# LTE.net
KiCad netlist of a schematic drawn in Altium Designer
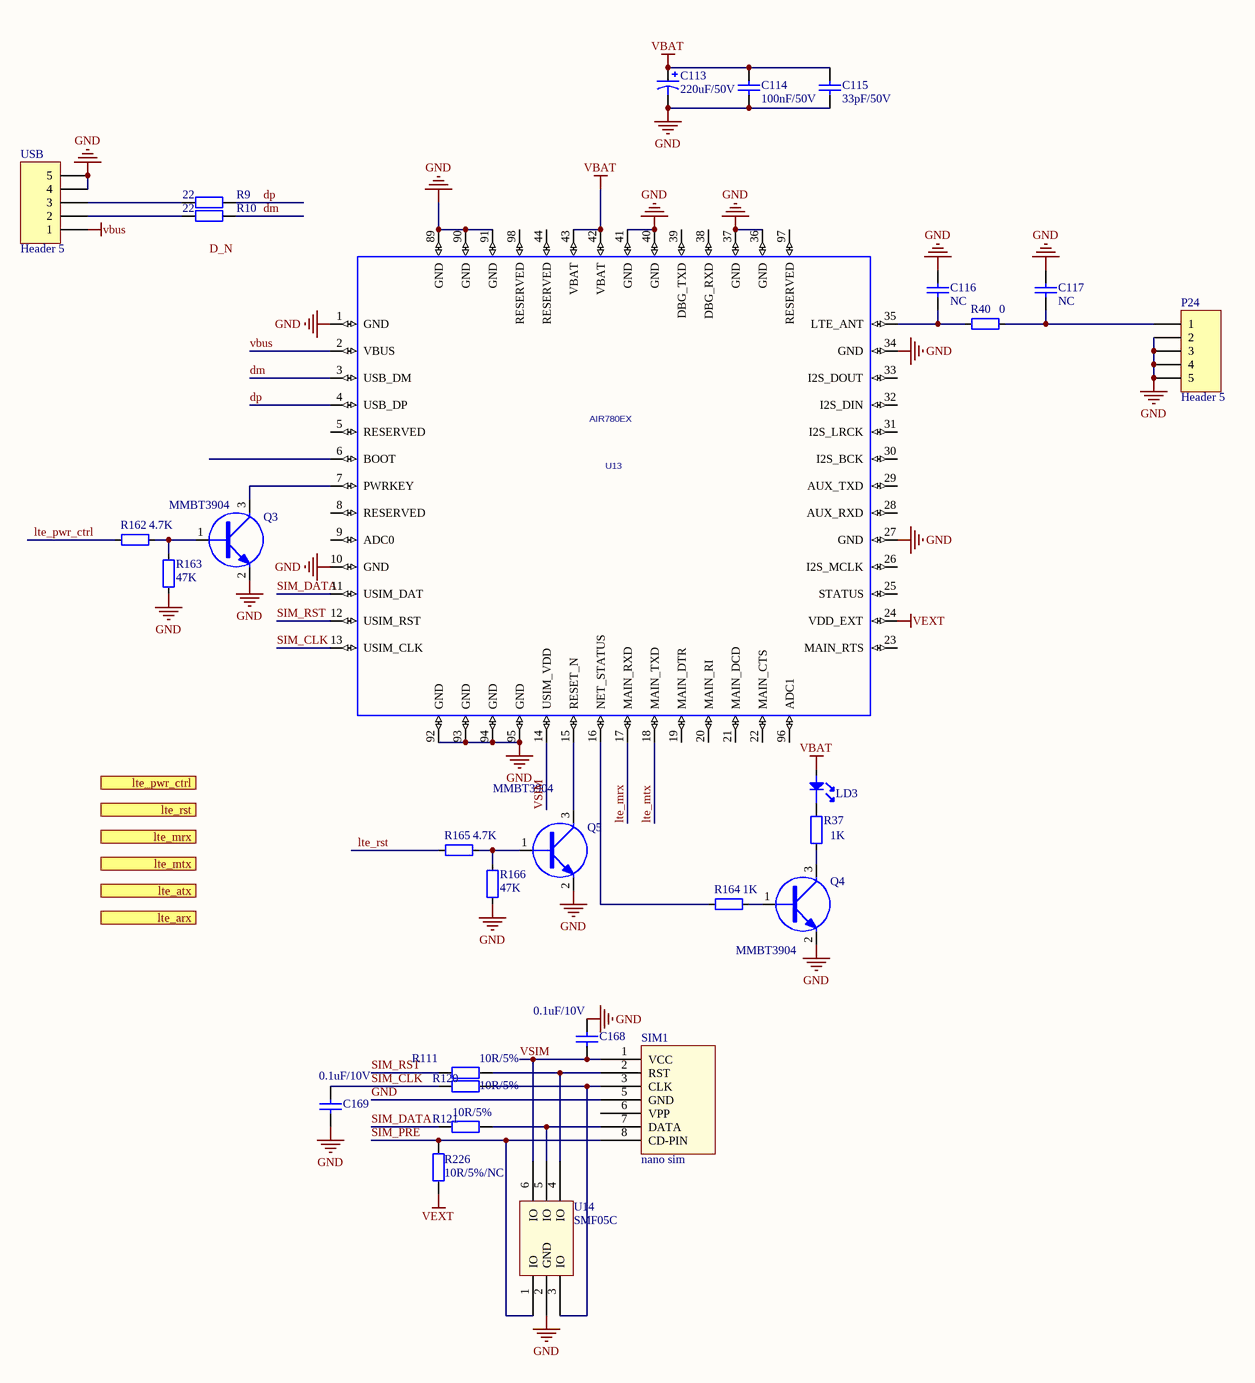
[diagram p0: LTE.SchDoc]

(export (version "E")
  (design (tool "Eeschema 10.0.6"))
  (components
    (comp (ref "C113")
      (value "220uF/50V")
      (footprint "Φ10×10")
      (description "Polarized Capacitor (Radial)")
      (fields (field (name "PUBLISHER") "Altium Limited"))
      (libsource (lib "Miscellaneous Devices") (part "Cap Pol1"))
    )
    (comp (ref "C114")
      (value "100nF/50V")
      (footprint "0603C")
      (description "Capacitor")
      (fields (field (name "PUBLISHER") "Altium Limited"))
      (libsource (lib "Miscellaneous Devices") (part "Cap"))
    )
    (comp (ref "C115")
      (value "33pF/50V")
      (footprint "0603C")
      (description "Capacitor")
      (fields (field (name "PUBLISHER") "Altium Limited"))
      (libsource (lib "Miscellaneous Devices") (part "Cap"))
    )
    (comp (ref "C116")
      (value "NC")
      (footprint "0603c")
      (description "Capacitor")
      (fields (field (name "PUBLISHER") "Altium Limited"))
      (libsource (lib "Miscellaneous Devices") (part "Cap"))
    )
    (comp (ref "C117")
      (value "NC")
      (footprint "0603c")
      (description "Capacitor")
      (fields (field (name "PUBLISHER") "Altium Limited"))
      (libsource (lib "Miscellaneous Devices") (part "Cap"))
    )
    (comp (ref "C168")
      (value "0.1uF/10V")
      (footprint "0603c")
      (description "Capacitor")
      (fields (field (name "PUBLISHER") "Altium Limited"))
      (libsource (lib "Miscellaneous Devices") (part "Cap"))
    )
    (comp (ref "C169")
      (value "0.1uF/10V")
      (footprint "0603c")
      (description "Capacitor")
      (fields (field (name "PUBLISHER") "Altium Limited"))
      (libsource (lib "Miscellaneous Devices") (part "Cap"))
    )
    (comp (ref "LD3")
      (value "LED_Green_19-217")
      (footprint "0603led")
      (libsource (lib "RC_M_D_00") (part "LED_Green_19-217"))
    )
    (comp (ref "P24")
      (value "Header 5")
      (footprint "KH-SMA-KE-Z")
      (description "Header, 5-Pin")
      (fields (field (name "PUBLISHER") "Altium Limited"))
      (libsource (lib "") (part "Header 5_1"))
    )
    (comp (ref "Q3")
      (value "MMBT3904")
      (footprint "SOT23-3")
      (libsource (lib "CenLib") (part "NPN_MMBT3904"))
    )
    (comp (ref "Q4")
      (value "MMBT3904")
      (footprint "SOT23-3")
      (libsource (lib "CenLib") (part "NPN_MMBT3904"))
    )
    (comp (ref "Q5")
      (value "MMBT3904")
      (footprint "SOT23-3")
      (libsource (lib "CenLib") (part "NPN_MMBT3904"))
    )
    (comp (ref "R9")
      (value "22")
      (footprint "0402R")
      (description "Resistor SMD - IEC symbol version")
      (libsource (lib "SX1276_e266v02a") (part "Resistor"))
    )
    (comp (ref "R10")
      (value "22")
      (footprint "0402R")
      (description "Resistor SMD - IEC symbol version")
      (libsource (lib "SX1276_e266v02a") (part "Resistor"))
    )
    (comp (ref "R37") (value "1K") (footprint "0603R") (libsource (lib "RC_M_D_00") (part "RES0603")))
    (comp (ref "R40") (value "0") (footprint "0603r") (libsource (lib "RC_M_D_00") (part "RES0603")))
    (comp (ref "R111")
      (value "10R/5%")
      (footprint "0603r")
      (description "Resistor")
      (fields (field (name "PUBLISHER") "Altium Limited"))
      (libsource (lib "Miscellaneous Devices") (part "Res2"))
    )
    (comp (ref "R120")
      (value "10R/5%")
      (footprint "0603r")
      (description "Resistor")
      (fields (field (name "PUBLISHER") "Altium Limited"))
      (libsource (lib "Miscellaneous Devices") (part "Res2"))
    )
    (comp (ref "R121")
      (value "10R/5%")
      (footprint "0603r")
      (description "Resistor")
      (fields (field (name "PUBLISHER") "Altium Limited"))
      (libsource (lib "Miscellaneous Devices") (part "Res2"))
    )
    (comp (ref "R162") (value "4.7K") (footprint "0603R") (libsource (lib "RC_M_D_00") (part "RES0603")))
    (comp (ref "R163") (value "47K") (footprint "0603r") (libsource (lib "RC_M_D_00") (part "RES0603")))
    (comp (ref "R164") (value "1K") (footprint "0603r") (libsource (lib "RC_M_D_00") (part "RES0603")))
    (comp (ref "R165") (value "4.7K") (footprint "0603R") (libsource (lib "RC_M_D_00") (part "RES0603")))
    (comp (ref "R166") (value "47K") (footprint "0603r") (libsource (lib "RC_M_D_00") (part "RES0603")))
    (comp (ref "R226")
      (value "10R/5%/NC")
      (footprint "0603r")
      (description "Resistor")
      (fields (field (name "PUBLISHER") "Altium Limited"))
      (libsource (lib "") (part "Res2_1"))
    )
    (comp (ref "SIM1") (value "nano sim") (footprint "Nano SIM") (libsource (lib "lm") (part "nano sim")))
    (comp (ref "U13")
      (value "AIR780EX")
      (footprint "Air780EX_AD:AIR780EX")
      (libsource (lib "*") (part "AIR780EX"))
    )
    (comp (ref "U14") (value "SMF05C") (footprint "sc70-6l") (libsource (lib "lm") (part "SMF05C")))
    (comp (ref "USB")
      (value "Header 5")
      (footprint "USB-MICRO-5P")
      (description "Header, 5-Pin")
      (fields (field (name "PUBLISHER") "Altium Limited"))
      (libsource (lib "Miscellaneous Connectors") (part "Header 5"))
    )
  )
  (nets
    (net (code "2") (name "/SIM_CLK") (class "Default")
      (node (ref "C169") (pin "1") (pinfunction "1_1") (pintype "passive"))
      (node (ref "R120") (pin "2") (pinfunction "2_2") (pintype "passive"))
      (node (ref "U13") (pin "13") (pinfunction "USIM_CLK_13") (pintype "bidirectional"))
    )
    (net (code "3") (name "/SIM_DATA") (class "Default")
      (node (ref "R121") (pin "2") (pinfunction "2_2") (pintype "passive"))
      (node (ref "U13") (pin "11") (pinfunction "USIM_DAT_11") (pintype "bidirectional"))
    )
    (net (code "4") (name "/SIM_PRE") (class "Default")
      (node (ref "R226") (pin "1") (pinfunction "1_1") (pintype "passive"))
      (node (ref "SIM1") (pin "8") (pinfunction "CD-PIN_8") (pintype "passive"))
      (node (ref "U14") (pin "1") (pinfunction "IO_1") (pintype "passive"))
    )
    (net (code "5") (name "/SIM_RST") (class "Default")
      (node (ref "R111") (pin "2") (pinfunction "2_2") (pintype "passive"))
      (node (ref "U13") (pin "12") (pinfunction "USIM_RST_12") (pintype "bidirectional"))
    )
    (net (code "6") (name "/VSIM") (class "Default")
      (node (ref "C168") (pin "2") (pinfunction "2_2") (pintype "passive"))
      (node (ref "SIM1") (pin "1") (pinfunction "VCC_1") (pintype "passive"))
      (node (ref "U13") (pin "14") (pinfunction "USIM_VDD_14") (pintype "bidirectional"))
      (node (ref "U14") (pin "6") (pinfunction "IO_6") (pintype "passive"))
    )
    (net (code "7") (name "/dm") (class "Default")
      (node (ref "R10") (pin "2") (pinfunction "2_2") (pintype "passive"))
      (node (ref "U13") (pin "3") (pinfunction "USB_DM_3") (pintype "bidirectional"))
    )
    (net (code "8") (name "/dp") (class "Default")
      (node (ref "R9") (pin "2") (pinfunction "2_2") (pintype "passive"))
      (node (ref "U13") (pin "4") (pinfunction "USB_DP_4") (pintype "bidirectional"))
    )
    (net (code "11") (name "/lte_mrx") (class "Default")
      (node (ref "U13") (pin "17") (pinfunction "MAIN_RXD_17") (pintype "bidirectional"))
    )
    (net (code "12") (name "/lte_mtx") (class "Default")
      (node (ref "U13") (pin "18") (pinfunction "MAIN_TXD_18") (pintype "bidirectional"))
    )
    (net (code "13") (name "/lte_pwr_ctrl") (class "Default")
      (node (ref "R162") (pin "1") (pinfunction "1_1") (pintype "passive"))
    )
    (net (code "14") (name "/lte_rst") (class "Default")
      (node (ref "R165") (pin "1") (pinfunction "1_1") (pintype "passive"))
    )
    (net (code "15") (name "GND") (class "Default")
      (node (ref "C113") (pin "2") (pinfunction "2_2") (pintype "passive"))
      (node (ref "C114") (pin "1") (pinfunction "1_1") (pintype "passive"))
      (node (ref "C115") (pin "1") (pinfunction "1_1") (pintype "passive"))
      (node (ref "C116") (pin "2") (pinfunction "2_2") (pintype "passive"))
      (node (ref "C117") (pin "2") (pinfunction "2_2") (pintype "passive"))
      (node (ref "C168") (pin "1") (pinfunction "1_1") (pintype "passive"))
      (node (ref "C169") (pin "2") (pinfunction "2_2") (pintype "passive"))
      (node (ref "P24") (pin "2") (pinfunction "2_2") (pintype "passive"))
      (node (ref "P24") (pin "3") (pinfunction "3_3") (pintype "passive"))
      (node (ref "P24") (pin "4") (pinfunction "4_4") (pintype "passive"))
      (node (ref "P24") (pin "5") (pinfunction "5_5") (pintype "passive"))
      (node (ref "Q3") (pin "2") (pinfunction "E_2") (pintype "passive"))
      (node (ref "Q4") (pin "2") (pinfunction "E_2") (pintype "passive"))
      (node (ref "Q5") (pin "2") (pinfunction "E_2") (pintype "passive"))
      (node (ref "R163") (pin "1") (pinfunction "1_1") (pintype "passive"))
      (node (ref "R166") (pin "1") (pinfunction "1_1") (pintype "passive"))
      (node (ref "SIM1") (pin "5") (pinfunction "GND_5") (pintype "passive"))
      (node (ref "U13") (pin "1") (pinfunction "GND_1") (pintype "bidirectional"))
      (node (ref "U13") (pin "10") (pinfunction "GND_10") (pintype "bidirectional"))
      (node (ref "U13") (pin "27") (pinfunction "GND_27") (pintype "bidirectional"))
      (node (ref "U13") (pin "34") (pinfunction "GND_34") (pintype "bidirectional"))
      (node (ref "U13") (pin "36") (pinfunction "GND_36") (pintype "bidirectional"))
      (node (ref "U13") (pin "37") (pinfunction "GND_37") (pintype "bidirectional"))
      (node (ref "U13") (pin "40") (pinfunction "GND_40") (pintype "bidirectional"))
      (node (ref "U13") (pin "41") (pinfunction "GND_41") (pintype "bidirectional"))
      (node (ref "U13") (pin "89") (pinfunction "GND_89") (pintype "bidirectional"))
      (node (ref "U13") (pin "90") (pinfunction "GND_90") (pintype "bidirectional"))
      (node (ref "U13") (pin "91") (pinfunction "GND_91") (pintype "bidirectional"))
      (node (ref "U13") (pin "92") (pinfunction "GND_92") (pintype "bidirectional"))
      (node (ref "U13") (pin "93") (pinfunction "GND_93") (pintype "bidirectional"))
      (node (ref "U13") (pin "94") (pinfunction "GND_94") (pintype "bidirectional"))
      (node (ref "U13") (pin "95") (pinfunction "GND_95") (pintype "bidirectional"))
      (node (ref "U14") (pin "2") (pinfunction "GND_2") (pintype "passive"))
      (node (ref "USB") (pin "4") (pinfunction "4_4") (pintype "passive"))
      (node (ref "USB") (pin "5") (pinfunction "5_5") (pintype "passive"))
    )
    (net (code "16") (name "Net-(C117-Pad1)") (class "Default")
      (node (ref "C117") (pin "1") (pinfunction "1_1") (pintype "passive"))
      (node (ref "P24") (pin "1") (pinfunction "1_1") (pintype "passive"))
      (node (ref "R40") (pin "2") (pinfunction "2_2") (pintype "passive"))
    )
    (net (code "17") (name "Net-(LD3-Pad2)") (class "Default")
      (node (ref "LD3") (pin "2") (pinfunction "2_2") (pintype "passive"))
      (node (ref "R37") (pin "1") (pinfunction "1_1") (pintype "passive"))
    )
    (net (code "18") (name "Net-(Q3-B)") (class "Default")
      (node (ref "Q3") (pin "1") (pinfunction "B_1") (pintype "passive"))
      (node (ref "R162") (pin "2") (pinfunction "2_2") (pintype "passive"))
      (node (ref "R163") (pin "2") (pinfunction "2_2") (pintype "passive"))
    )
    (net (code "19") (name "Net-(Q3-C)") (class "Default")
      (node (ref "Q3") (pin "3") (pinfunction "C_3") (pintype "passive"))
      (node (ref "U13") (pin "7") (pinfunction "PWRKEY_7") (pintype "bidirectional"))
    )
    (net (code "20") (name "Net-(Q4-B)") (class "Default")
      (node (ref "Q4") (pin "1") (pinfunction "B_1") (pintype "passive"))
      (node (ref "R164") (pin "2") (pinfunction "2_2") (pintype "passive"))
    )
    (net (code "21") (name "Net-(Q4-C)") (class "Default")
      (node (ref "Q4") (pin "3") (pinfunction "C_3") (pintype "passive"))
      (node (ref "R37") (pin "2") (pinfunction "2_2") (pintype "passive"))
    )
    (net (code "22") (name "Net-(Q5-B)") (class "Default")
      (node (ref "Q5") (pin "1") (pinfunction "B_1") (pintype "passive"))
      (node (ref "R165") (pin "2") (pinfunction "2_2") (pintype "passive"))
      (node (ref "R166") (pin "2") (pinfunction "2_2") (pintype "passive"))
    )
    (net (code "23") (name "Net-(Q5-C)") (class "Default")
      (node (ref "Q5") (pin "3") (pinfunction "C_3") (pintype "passive"))
      (node (ref "U13") (pin "15") (pinfunction "RESET_N_15") (pintype "bidirectional"))
    )
    (net (code "24") (name "Net-(R9-Pad1)") (class "Default")
      (node (ref "R9") (pin "1") (pinfunction "1_1") (pintype "passive"))
      (node (ref "USB") (pin "3") (pinfunction "3_3") (pintype "passive"))
    )
    (net (code "25") (name "Net-(R10-Pad1)") (class "Default")
      (node (ref "R10") (pin "1") (pinfunction "1_1") (pintype "passive"))
      (node (ref "USB") (pin "2") (pinfunction "2_2") (pintype "passive"))
    )
    (net (code "26") (name "Net-(SIM1-CLK)") (class "Default")
      (node (ref "R120") (pin "1") (pinfunction "1_1") (pintype "passive"))
      (node (ref "SIM1") (pin "3") (pinfunction "CLK_3") (pintype "passive"))
      (node (ref "U14") (pin "3") (pinfunction "IO_3") (pintype "passive"))
    )
    (net (code "27") (name "Net-(SIM1-DATA)") (class "Default")
      (node (ref "R121") (pin "1") (pinfunction "1_1") (pintype "passive"))
      (node (ref "SIM1") (pin "7") (pinfunction "DATA_7") (pintype "passive"))
      (node (ref "U14") (pin "5") (pinfunction "IO_5") (pintype "passive"))
    )
    (net (code "28") (name "Net-(SIM1-RST)") (class "Default")
      (node (ref "R111") (pin "1") (pinfunction "1_1") (pintype "passive"))
      (node (ref "SIM1") (pin "2") (pinfunction "RST_2") (pintype "passive"))
      (node (ref "U14") (pin "4") (pinfunction "IO_4") (pintype "passive"))
    )
    (net (code "29") (name "Net-(U13-LTE_ANT)") (class "Default")
      (node (ref "C116") (pin "1") (pinfunction "1_1") (pintype "passive"))
      (node (ref "R40") (pin "1") (pinfunction "1_1") (pintype "passive"))
      (node (ref "U13") (pin "35") (pinfunction "LTE_ANT_35") (pintype "bidirectional"))
    )
    (net (code "30") (name "Net-(U13-NET_STATUS)") (class "Default")
      (node (ref "R164") (pin "1") (pinfunction "1_1") (pintype "passive"))
      (node (ref "U13") (pin "16") (pinfunction "NET_STATUS_16") (pintype "bidirectional"))
    )
    (net (code "31") (name "VBAT") (class "Default")
      (node (ref "C113") (pin "1") (pinfunction "1_1") (pintype "passive"))
      (node (ref "C114") (pin "2") (pinfunction "2_2") (pintype "passive"))
      (node (ref "C115") (pin "2") (pinfunction "2_2") (pintype "passive"))
      (node (ref "LD3") (pin "1") (pinfunction "1_1") (pintype "passive"))
      (node (ref "U13") (pin "42") (pinfunction "VBAT_42") (pintype "bidirectional"))
      (node (ref "U13") (pin "43") (pinfunction "VBAT_43") (pintype "bidirectional"))
    )
    (net (code "32") (name "VEXT") (class "Default")
      (node (ref "R226") (pin "2") (pinfunction "2_2") (pintype "passive"))
      (node (ref "U13") (pin "24") (pinfunction "VDD_EXT_24") (pintype "bidirectional"))
    )
    (net (code "33") (name "unconnected-(SIM1-VPP-Pad6)") (class "Default")
      (node (ref "SIM1") (pin "6") (pinfunction "VPP_6") (pintype "passive"))
    )
    (net (code "34") (name "unconnected-(U13-ADC0-Pad9)") (class "Default")
      (node (ref "U13") (pin "9") (pinfunction "ADC0_9") (pintype "bidirectional"))
    )
    (net (code "35") (name "unconnected-(U13-ADC1-Pad96)") (class "Default")
      (node (ref "U13") (pin "96") (pinfunction "ADC1_96") (pintype "bidirectional"))
    )
    (net (code "36") (name "unconnected-(U13-AUX_RXD-Pad28)") (class "Default")
      (node (ref "U13") (pin "28") (pinfunction "AUX_RXD_28") (pintype "bidirectional"))
    )
    (net (code "37") (name "unconnected-(U13-AUX_TXD-Pad29)") (class "Default")
      (node (ref "U13") (pin "29") (pinfunction "AUX_TXD_29") (pintype "bidirectional"))
    )
    (net (code "38") (name "unconnected-(U13-BOOT-Pad6)") (class "Default")
      (node (ref "U13") (pin "6") (pinfunction "BOOT_6") (pintype "bidirectional"))
    )
    (net (code "39") (name "unconnected-(U13-DBG_RXD-Pad38)") (class "Default")
      (node (ref "U13") (pin "38") (pinfunction "DBG_RXD_38") (pintype "bidirectional"))
    )
    (net (code "40") (name "unconnected-(U13-DBG_TXD-Pad39)") (class "Default")
      (node (ref "U13") (pin "39") (pinfunction "DBG_TXD_39") (pintype "bidirectional"))
    )
    (net (code "41") (name "unconnected-(U13-I2S_BCK-Pad30)") (class "Default")
      (node (ref "U13") (pin "30") (pinfunction "I2S_BCK_30") (pintype "bidirectional"))
    )
    (net (code "42") (name "unconnected-(U13-I2S_DIN-Pad32)") (class "Default")
      (node (ref "U13") (pin "32") (pinfunction "I2S_DIN_32") (pintype "bidirectional"))
    )
    (net (code "43") (name "unconnected-(U13-I2S_DOUT-Pad33)") (class "Default")
      (node (ref "U13") (pin "33") (pinfunction "I2S_DOUT_33") (pintype "bidirectional"))
    )
    (net (code "44") (name "unconnected-(U13-I2S_LRCK-Pad31)") (class "Default")
      (node (ref "U13") (pin "31") (pinfunction "I2S_LRCK_31") (pintype "bidirectional"))
    )
    (net (code "45") (name "unconnected-(U13-I2S_MCLK-Pad26)") (class "Default")
      (node (ref "U13") (pin "26") (pinfunction "I2S_MCLK_26") (pintype "bidirectional"))
    )
    (net (code "46") (name "unconnected-(U13-MAIN_CTS-Pad22)") (class "Default")
      (node (ref "U13") (pin "22") (pinfunction "MAIN_CTS_22") (pintype "bidirectional"))
    )
    (net (code "47") (name "unconnected-(U13-MAIN_DCD-Pad21)") (class "Default")
      (node (ref "U13") (pin "21") (pinfunction "MAIN_DCD_21") (pintype "bidirectional"))
    )
    (net (code "48") (name "unconnected-(U13-MAIN_DTR-Pad19)") (class "Default")
      (node (ref "U13") (pin "19") (pinfunction "MAIN_DTR_19") (pintype "bidirectional"))
    )
    (net (code "49") (name "unconnected-(U13-MAIN_RI-Pad20)") (class "Default")
      (node (ref "U13") (pin "20") (pinfunction "MAIN_RI_20") (pintype "bidirectional"))
    )
    (net (code "50") (name "unconnected-(U13-MAIN_RTS-Pad23)") (class "Default")
      (node (ref "U13") (pin "23") (pinfunction "MAIN_RTS_23") (pintype "bidirectional"))
    )
    (net (code "51") (name "unconnected-(U13-RESERVED-Pad5)") (class "Default")
      (node (ref "U13") (pin "5") (pinfunction "RESERVED_5") (pintype "bidirectional"))
    )
    (net (code "52") (name "unconnected-(U13-RESERVED-Pad8)") (class "Default")
      (node (ref "U13") (pin "8") (pinfunction "RESERVED_8") (pintype "bidirectional"))
    )
    (net (code "53") (name "unconnected-(U13-RESERVED-Pad44)") (class "Default")
      (node (ref "U13") (pin "44") (pinfunction "RESERVED_44") (pintype "bidirectional"))
    )
    (net (code "54") (name "unconnected-(U13-RESERVED-Pad97)") (class "Default")
      (node (ref "U13") (pin "97") (pinfunction "RESERVED_97") (pintype "bidirectional"))
    )
    (net (code "55") (name "unconnected-(U13-RESERVED-Pad98)") (class "Default")
      (node (ref "U13") (pin "98") (pinfunction "RESERVED_98") (pintype "bidirectional"))
    )
    (net (code "56") (name "unconnected-(U13-STATUS-Pad25)") (class "Default")
      (node (ref "U13") (pin "25") (pinfunction "STATUS_25") (pintype "bidirectional"))
    )
    (net (code "57") (name "vbus") (class "Default")
      (node (ref "U13") (pin "2") (pinfunction "VBUS_2") (pintype "bidirectional"))
      (node (ref "USB") (pin "1") (pinfunction "1_1") (pintype "passive"))
    )
  )
)
